# usb.net
KiCad netlist of a schematic drawn in Altium Designer
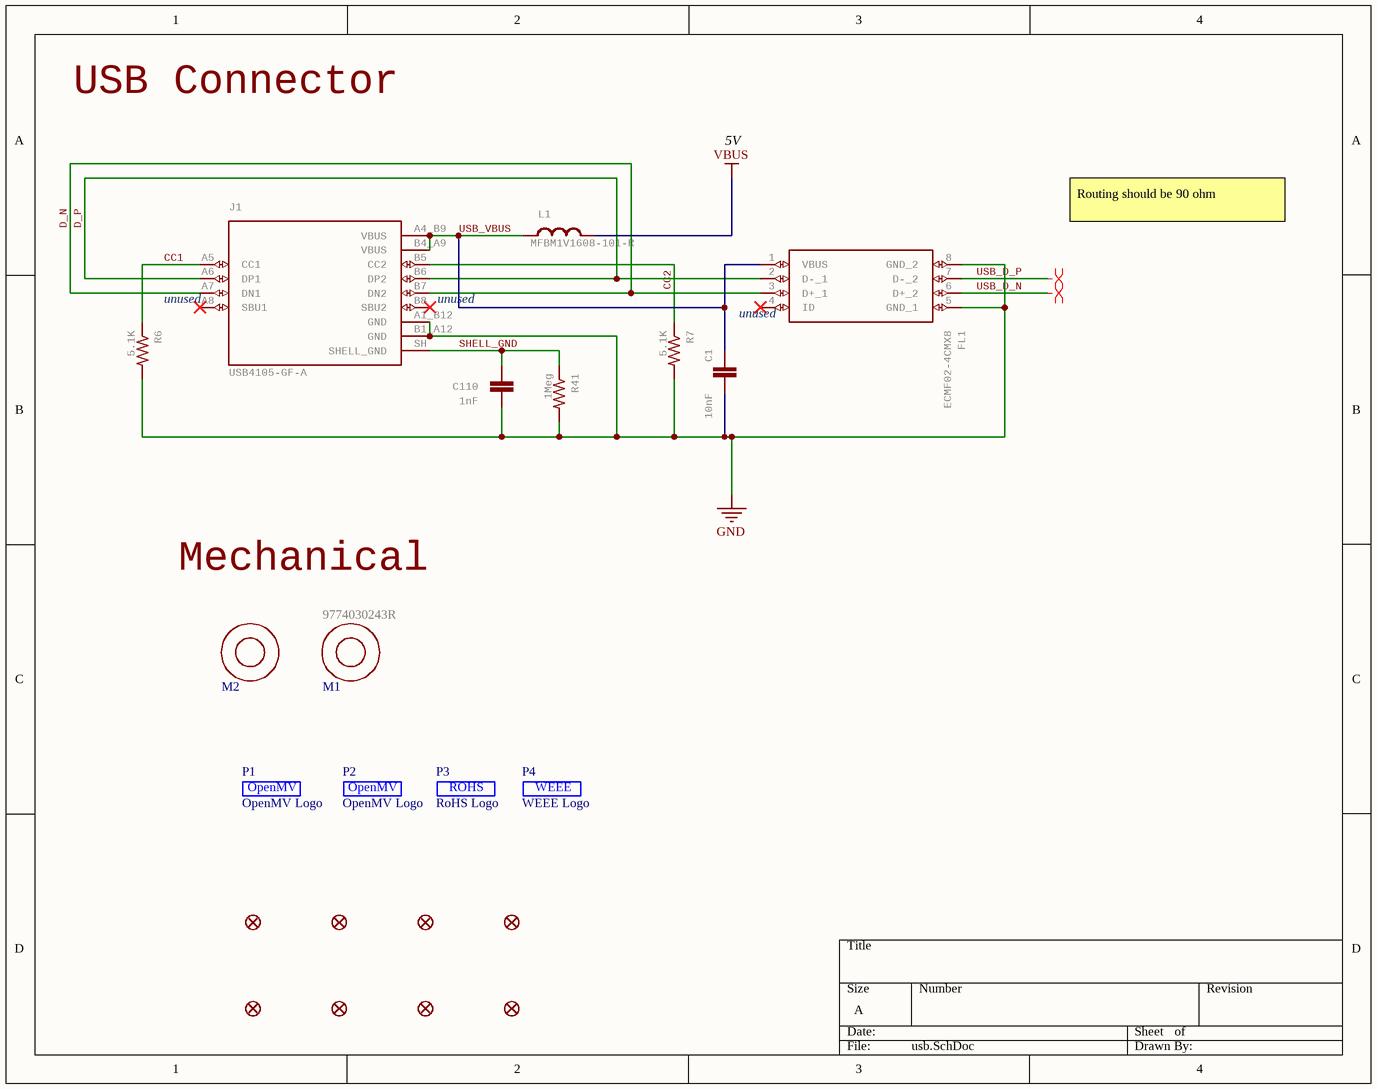
[diagram p0: usb.SchDoc]

(export (version "E")
  (design (tool "Eeschema 10.0.6"))
  (components
    (comp (ref "C1")
      (value "10nF")
      (footprint "0402-CAP")
      (description "CAPACITOR, European symbol")
      (fields (field (name "MPN") "0402B103K250CT"))
      (libsource (lib "openmv-ae3") (part "C-EUC0201"))
    )
    (comp (ref "C110")
      (value "1nF")
      (footprint "0402-CAP")
      (description "Capacitor")
      (fields (field (name "MPN") "VJ0402Y102JXACW1BC"))
      (libsource (lib "rt10") (part "CAP0402-CAP"))
    )
    (comp (ref "FD1")
      (value "FIDUCIAL1X2")
      (footprint "FIDUCIAL-1X2")
      (fields (field (name "LIBRARYNAME") "SparkFun-Aesthetics"))
      (libsource (lib "rt10") (part "FIDUCIAL1X2"))
    )
    (comp (ref "FD2")
      (value "FIDUCIAL1X2")
      (footprint "FIDUCIAL-1X2")
      (fields (field (name "LIBRARYNAME") "SparkFun-Aesthetics"))
      (libsource (lib "rt10") (part "FIDUCIAL1X2"))
    )
    (comp (ref "FD3")
      (value "FIDUCIAL1X2")
      (footprint "FIDUCIAL-1X2")
      (fields (field (name "LIBRARYNAME") "SparkFun-Aesthetics"))
      (libsource (lib "rt10") (part "FIDUCIAL1X2"))
    )
    (comp (ref "FD4")
      (value "FIDUCIAL1X2")
      (footprint "FIDUCIAL-1X2")
      (fields (field (name "LIBRARYNAME") "SparkFun-Aesthetics"))
      (libsource (lib "rt10") (part "FIDUCIAL1X2"))
    )
    (comp (ref "FD5")
      (value "FIDUCIAL1X2")
      (footprint "FIDUCIAL-1X2")
      (fields (field (name "LIBRARYNAME") "SparkFun-Aesthetics"))
      (libsource (lib "rt10") (part "FIDUCIAL1X2"))
    )
    (comp (ref "FD6")
      (value "FIDUCIAL1X2")
      (footprint "FIDUCIAL-1X2")
      (fields (field (name "LIBRARYNAME") "SparkFun-Aesthetics"))
      (libsource (lib "rt10") (part "FIDUCIAL1X2"))
    )
    (comp (ref "FD7")
      (value "FIDUCIAL1X2")
      (footprint "FIDUCIAL-1X2")
      (fields (field (name "LIBRARYNAME") "SparkFun-Aesthetics"))
      (libsource (lib "rt10") (part "FIDUCIAL1X2"))
    )
    (comp (ref "FD8")
      (value "FIDUCIAL1X2")
      (footprint "FIDUCIAL-1X2")
      (fields (field (name "LIBRARYNAME") "SparkFun-Aesthetics"))
      (libsource (lib "rt10") (part "FIDUCIAL1X2"))
    )
    (comp (ref "FL1")
      (value "ECMF02-4CMX8")
      (footprint "ECMF024CMX8")
      (fields (field (name "MOUSER_PART_NUMBER") "511-ECMF02-4CMX8"))
      (libsource (lib "rt10") (part "ECMF02-4CMX8"))
    )
    (comp (ref "J1")
      (value "USB4105-GF-A")
      (footprint "GCT_USB4105-GF-A")
      (fields (field (name "MF") "GCT"))
      (libsource (lib "rt10") (part "USB4105-GF-A"))
    )
    (comp (ref "L1")
      (value "MFBM1V1608-101-R")
      (footprint "0603-RES")
      (libsource (lib "rt10") (part "INDUCTOR"))
    )
    (comp (ref "M1")
      (value "9774030243R")
      (footprint "9774030243R")
      (description "M2 3mm Standoff")
      (libsource (lib "rt10") (part "9774030243R"))
    )
    (comp (ref "M2")
      (value "9774030243R")
      (footprint "9774030243R")
      (description "M2 3mm Standoff")
      (libsource (lib "rt10") (part "9774030243R"))
    )
    (comp (ref "P1") (value "OpenMV Logo") (footprint "OMV-LOGO-SMALL") (libsource (lib "rt10") (part "OMV")))
    (comp (ref "P2") (value "OpenMV Logo") (footprint "OMV-LOGO-SMALL") (libsource (lib "rt10") (part "OMV")))
    (comp (ref "P3") (value "RoHS Logo") (footprint "ROHS") (libsource (lib "rt10") (part "ROHS")))
    (comp (ref "P4") (value "WEEE Logo") (footprint "WEEE") (libsource (lib "rt10") (part "WEEE")))
    (comp (ref "R6")
      (value "5.1K")
      (footprint "0402-RES")
      (description "ResistorBasic schematic elements and footprints for 0603, 1206, and PTH resistors.")
      (fields (field (name "MPN") "RC0402JR-075K1L"))
      (libsource (lib "rt10") (part "RESISTOR0402-RES"))
    )
    (comp (ref "R7")
      (value "5.1K")
      (footprint "0402-RES")
      (description "ResistorBasic schematic elements and footprints for 0603, 1206, and PTH resistors.")
      (fields (field (name "MPN") "RC0402JR-075K1L"))
      (libsource (lib "rt10") (part "RESISTOR0402-RES"))
    )
    (comp (ref "R41")
      (value "1Meg")
      (footprint "0402-RES")
      (description "Resistor")
      (fields (field (name "MPN") "CRCW04021M00FKEDC"))
      (libsource (lib "rt10") (part "RESISTOR0402-RES"))
    )
  )
  (nets
    (net (code "1") (name "/CC1") (class "Default")
      (node (ref "J1") (pin "A5") (pinfunction "CC1_A5") (pintype "bidirectional"))
      (node (ref "R6") (pin "1") (pinfunction "1_1") (pintype "passive"))
    )
    (net (code "2") (name "/CC2") (class "Default")
      (node (ref "J1") (pin "B5") (pinfunction "CC2_B5") (pintype "bidirectional"))
      (node (ref "R7") (pin "1") (pinfunction "1_1") (pintype "passive"))
    )
    (net (code "3") (name "/D_N") (class "Default")
      (node (ref "FL1") (pin "3") (pinfunction "D+_1_3") (pintype "bidirectional"))
      (node (ref "J1") (pin "A7") (pinfunction "DN1_A7") (pintype "bidirectional"))
      (node (ref "J1") (pin "B7") (pinfunction "DN2_B7") (pintype "bidirectional"))
    )
    (net (code "4") (name "/D_P") (class "Default")
      (node (ref "FL1") (pin "2") (pinfunction "D-_1_2") (pintype "bidirectional"))
      (node (ref "J1") (pin "A6") (pinfunction "DP1_A6") (pintype "bidirectional"))
      (node (ref "J1") (pin "B6") (pinfunction "DP2_B6") (pintype "bidirectional"))
    )
    (net (code "5") (name "/SHELL_GND") (class "Default")
      (node (ref "C110") (pin "1") (pinfunction "1_1") (pintype "passive"))
      (node (ref "J1") (pin "SH") (pinfunction "SHELL_GND_SH") (pintype "power_in"))
      (node (ref "R41") (pin "1") (pinfunction "1_1") (pintype "passive"))
    )
    (net (code "6") (name "/USB_D_N") (class "Default")
      (node (ref "FL1") (pin "6") (pinfunction "D+_2_6") (pintype "bidirectional"))
    )
    (net (code "7") (name "/USB_D_P") (class "Default")
      (node (ref "FL1") (pin "7") (pinfunction "D-_2_7") (pintype "bidirectional"))
    )
    (net (code "8") (name "/USB_VBUS") (class "Default")
      (node (ref "C1") (pin "1") (pinfunction "1_1") (pintype "passive"))
      (node (ref "FL1") (pin "1") (pinfunction "VBUS_1") (pintype "bidirectional"))
      (node (ref "J1") (pin "A4_B9") (pinfunction "VBUS_A4_B9") (pintype "power_in"))
      (node (ref "J1") (pin "B4_A9") (pinfunction "VBUS_B4_A9") (pintype "power_in"))
      (node (ref "L1") (pin "1") (pinfunction "1_1") (pintype "passive"))
    )
    (net (code "9") (name "GND") (class "Default")
      (node (ref "C1") (pin "2") (pinfunction "2_2") (pintype "passive"))
      (node (ref "C110") (pin "2") (pinfunction "2_2") (pintype "passive"))
      (node (ref "FL1") (pin "5") (pinfunction "GND_1_5") (pintype "bidirectional"))
      (node (ref "FL1") (pin "8") (pinfunction "GND_2_8") (pintype "bidirectional"))
      (node (ref "J1") (pin "A1_B12") (pinfunction "GND_A1_B12") (pintype "power_in"))
      (node (ref "J1") (pin "B1_A12") (pinfunction "GND_B1_A12") (pintype "power_in"))
      (node (ref "R41") (pin "2") (pinfunction "2_2") (pintype "passive"))
      (node (ref "R6") (pin "2") (pinfunction "2_2") (pintype "passive"))
      (node (ref "R7") (pin "2") (pinfunction "2_2") (pintype "passive"))
    )
    (net (code "10") (name "VBUS") (class "Default")
      (node (ref "L1") (pin "2") (pinfunction "2_2") (pintype "passive"))
    )
    (net (code "11") (name "unconnected-(FL1-ID-Pad4)") (class "Default")
      (node (ref "FL1") (pin "4") (pinfunction "ID_4") (pintype "bidirectional+no_connect"))
    )
    (net (code "12") (name "unconnected-(J1-SBU1-PadA8)") (class "Default")
      (node (ref "J1") (pin "A8") (pinfunction "SBU1_A8") (pintype "bidirectional+no_connect"))
    )
    (net (code "13") (name "unconnected-(J1-SBU2-PadB8)") (class "Default")
      (node (ref "J1") (pin "B8") (pinfunction "SBU2_B8") (pintype "bidirectional+no_connect"))
    )
  )
)
